# Impression5-SMASH-Shield.net
KiCad netlist of a schematic drawn in EAGLE
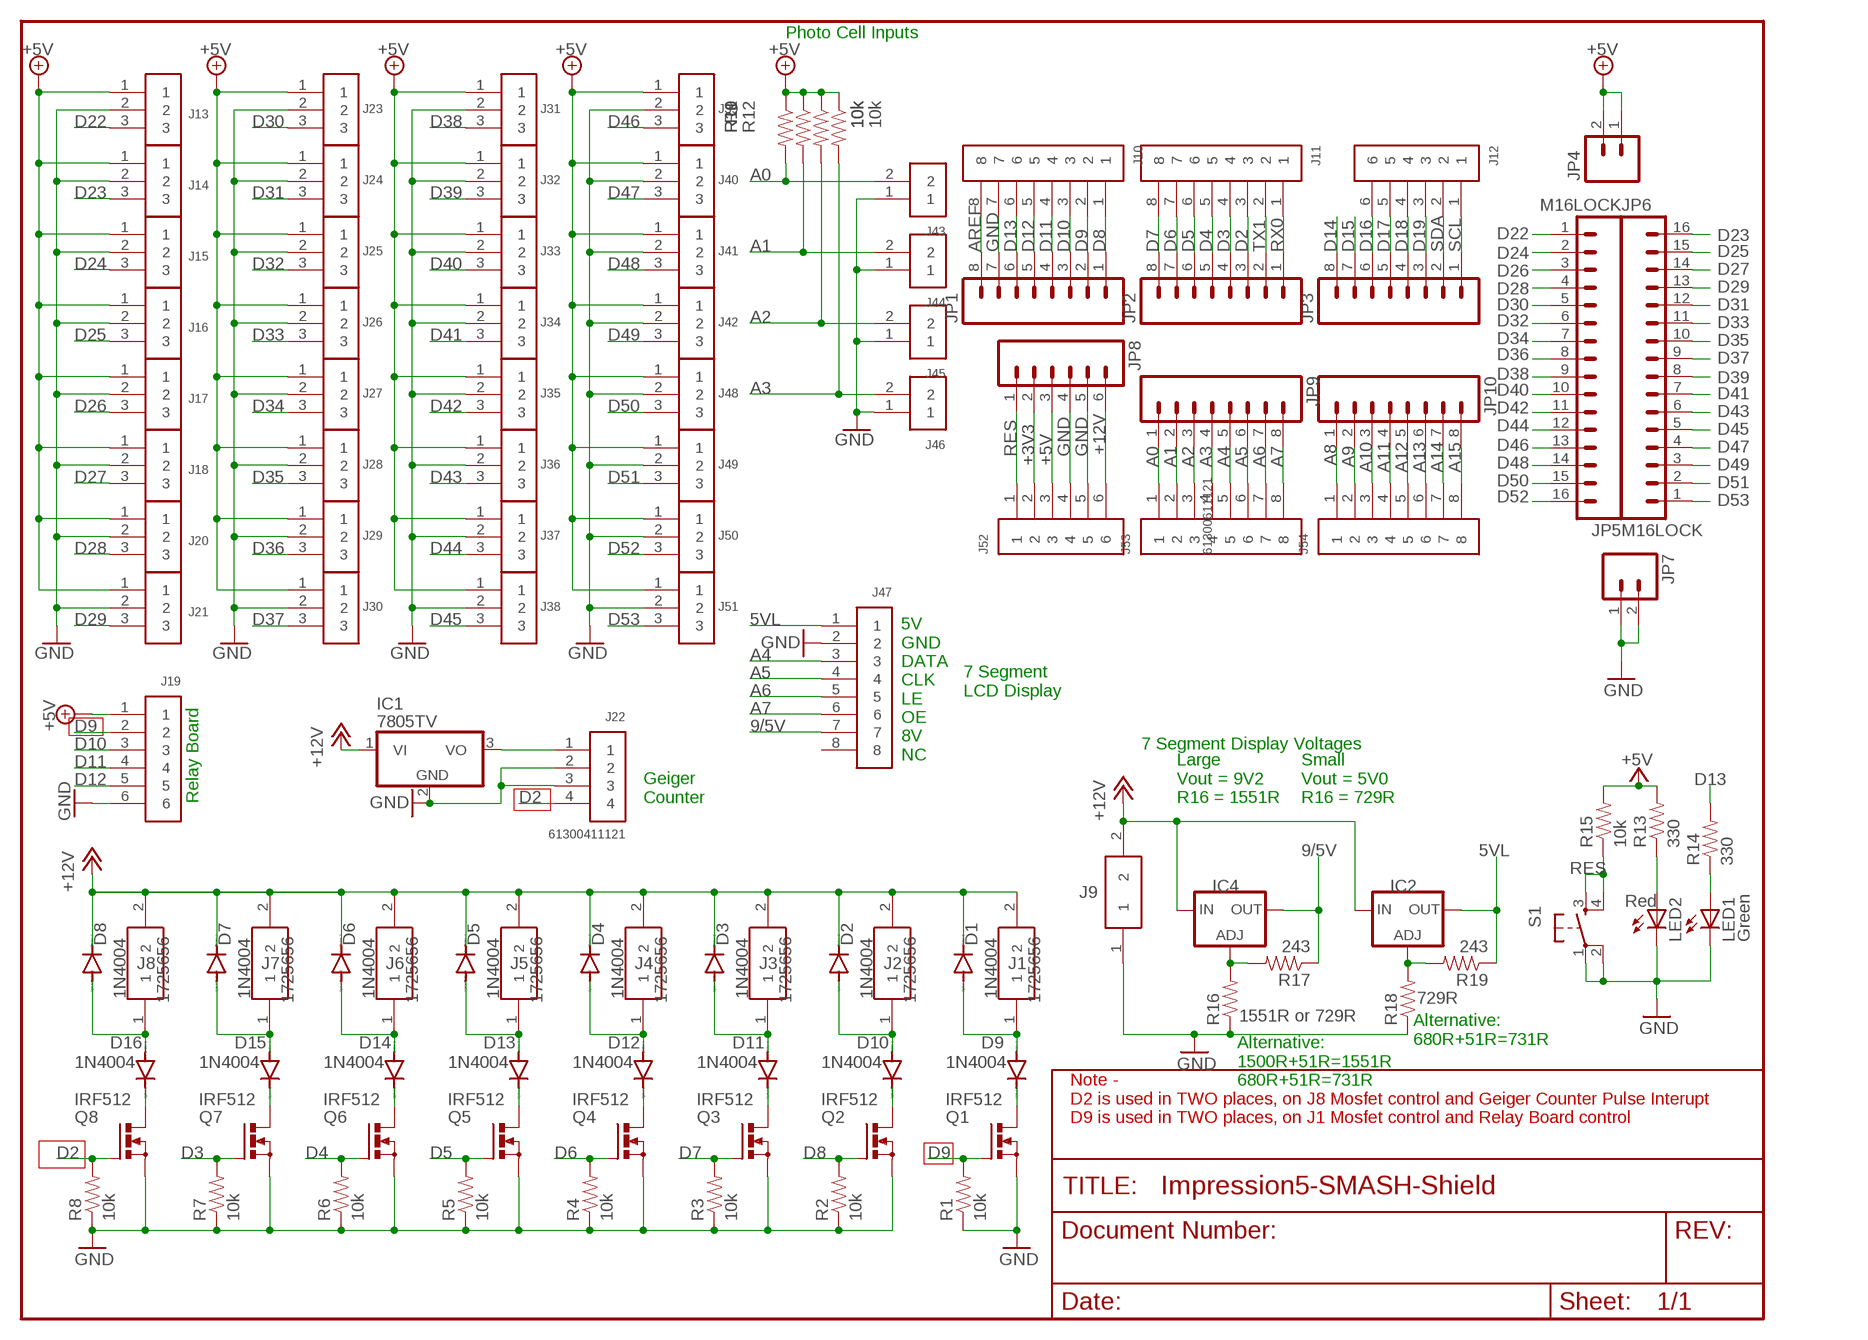
[diagram p0: schematic, sheet 1]

(export (version "E")
  (design (tool "Eeschema 10.0.6"))
  (components
    (comp (ref "D1")
      (value "1N4004")
      (footprint "eagle-import:DO41-10")
      (libsource (lib "eagle-import") (part "1N4004"))
    )
    (comp (ref "D2")
      (value "1N4004")
      (footprint "eagle-import:DO41-10")
      (libsource (lib "eagle-import") (part "1N4004"))
    )
    (comp (ref "D3")
      (value "1N4004")
      (footprint "eagle-import:DO41-10")
      (libsource (lib "eagle-import") (part "1N4004"))
    )
    (comp (ref "D4")
      (value "1N4004")
      (footprint "eagle-import:DO41-10")
      (libsource (lib "eagle-import") (part "1N4004"))
    )
    (comp (ref "D5")
      (value "1N4004")
      (footprint "eagle-import:DO41-10")
      (libsource (lib "eagle-import") (part "1N4004"))
    )
    (comp (ref "D6")
      (value "1N4004")
      (footprint "eagle-import:DO41-10")
      (libsource (lib "eagle-import") (part "1N4004"))
    )
    (comp (ref "D7")
      (value "1N4004")
      (footprint "eagle-import:DO41-10")
      (libsource (lib "eagle-import") (part "1N4004"))
    )
    (comp (ref "D8")
      (value "1N4004")
      (footprint "eagle-import:DO41-10")
      (libsource (lib "eagle-import") (part "1N4004"))
    )
    (comp (ref "D9")
      (value "1N4004")
      (footprint "eagle-import:DO41-10")
      (libsource (lib "eagle-import") (part "1N4004"))
    )
    (comp (ref "D10")
      (value "1N4004")
      (footprint "eagle-import:DO41-10")
      (libsource (lib "eagle-import") (part "1N4004"))
    )
    (comp (ref "D11")
      (value "1N4004")
      (footprint "eagle-import:DO41-10")
      (libsource (lib "eagle-import") (part "1N4004"))
    )
    (comp (ref "D12")
      (value "1N4004")
      (footprint "eagle-import:DO41-10")
      (libsource (lib "eagle-import") (part "1N4004"))
    )
    (comp (ref "D13")
      (value "1N4004")
      (footprint "eagle-import:DO41-10")
      (libsource (lib "eagle-import") (part "1N4004"))
    )
    (comp (ref "D14")
      (value "1N4004")
      (footprint "eagle-import:DO41-10")
      (libsource (lib "eagle-import") (part "1N4004"))
    )
    (comp (ref "D15")
      (value "1N4004")
      (footprint "eagle-import:DO41-10")
      (libsource (lib "eagle-import") (part "1N4004"))
    )
    (comp (ref "D16")
      (value "1N4004")
      (footprint "eagle-import:DO41-10")
      (libsource (lib "eagle-import") (part "1N4004"))
    )
    (comp (ref "IC1")
      (value "7805TV")
      (footprint "eagle-import:TO220V")
      (libsource (lib "eagle-import") (part "78TV05"))
    )
    (comp (ref "IC2")
      (value "LM317TS")
      (footprint "eagle-import:317TS")
      (libsource (lib "eagle-import") (part "LM317TS"))
    )
    (comp (ref "IC4")
      (value "LM317TS")
      (footprint "eagle-import:317TS")
      (libsource (lib "eagle-import") (part "LM317TS"))
    )
    (comp (ref "J1")
      (value "1725656")
      (footprint "eagle-import:1725656")
      (fields (field (name "MOUSER_PART_NUMBER") "651-1725656") (field (name "RS_PART_NUMBER") "3909023"))
      (libsource (lib "eagle-import") (part "1725656"))
    )
    (comp (ref "J2")
      (value "1725656")
      (footprint "eagle-import:1725656")
      (fields (field (name "MOUSER_PART_NUMBER") "651-1725656") (field (name "RS_PART_NUMBER") "3909023"))
      (libsource (lib "eagle-import") (part "1725656"))
    )
    (comp (ref "J3")
      (value "1725656")
      (footprint "eagle-import:1725656")
      (fields (field (name "MOUSER_PART_NUMBER") "651-1725656") (field (name "RS_PART_NUMBER") "3909023"))
      (libsource (lib "eagle-import") (part "1725656"))
    )
    (comp (ref "J4")
      (value "1725656")
      (footprint "eagle-import:1725656")
      (fields (field (name "MOUSER_PART_NUMBER") "651-1725656") (field (name "RS_PART_NUMBER") "3909023"))
      (libsource (lib "eagle-import") (part "1725656"))
    )
    (comp (ref "J5")
      (value "1725656")
      (footprint "eagle-import:1725656")
      (fields (field (name "MOUSER_PART_NUMBER") "651-1725656") (field (name "RS_PART_NUMBER") "3909023"))
      (libsource (lib "eagle-import") (part "1725656"))
    )
    (comp (ref "J6")
      (value "1725656")
      (footprint "eagle-import:1725656")
      (fields (field (name "MOUSER_PART_NUMBER") "651-1725656") (field (name "RS_PART_NUMBER") "3909023"))
      (libsource (lib "eagle-import") (part "1725656"))
    )
    (comp (ref "J7")
      (value "1725656")
      (footprint "eagle-import:1725656")
      (fields (field (name "MOUSER_PART_NUMBER") "651-1725656") (field (name "RS_PART_NUMBER") "3909023"))
      (libsource (lib "eagle-import") (part "1725656"))
    )
    (comp (ref "J8")
      (value "1725656")
      (footprint "eagle-import:1725656")
      (fields (field (name "MOUSER_PART_NUMBER") "651-1725656") (field (name "RS_PART_NUMBER") "3909023"))
      (libsource (lib "eagle-import") (part "1725656"))
    )
    (comp (ref "J9")
      (value "1725656")
      (footprint "eagle-import:1725656")
      (fields (field (name "MOUSER_PART_NUMBER") "651-1725656") (field (name "RS_PART_NUMBER") "3909023"))
      (libsource (lib "eagle-import") (part "1725656"))
    )
    (comp (ref "J10")
      (value "61300811121")
      (footprint "eagle-import:61300811121")
      (fields
        (field (name "DIGI_KEY_PART_NUMBER") "732-5321-ND")
        (field (name "MANUFACTURER") "Wurth Electronics Inc.")
      )
      (libsource (lib "eagle-import") (part "61300811121"))
    )
    (comp (ref "J11")
      (value "61300811121")
      (footprint "eagle-import:61300811121")
      (fields
        (field (name "DIGI_KEY_PART_NUMBER") "732-5321-ND")
        (field (name "MANUFACTURER") "Wurth Electronics Inc.")
      )
      (libsource (lib "eagle-import") (part "61300811121"))
    )
    (comp (ref "J12")
      (value "61300611121")
      (footprint "eagle-import:61300611121")
      (fields
        (field (name "DIGI_KEY_PART_NUMBER") "732-5319-ND")
        (field (name "MANUFACTURER") "Wurth Electronics Inc.")
      )
      (libsource (lib "eagle-import") (part "61300611121"))
    )
    (comp (ref "J13")
      (value "61300311121")
      (footprint "eagle-import:61300311121")
      (fields
        (field (name "DIGI_KEY_PART_NUMBER") "732-5316-ND")
        (field (name "MANUFACTURER") "Wurth Electronics Inc.")
      )
      (libsource (lib "eagle-import") (part "61300311121"))
    )
    (comp (ref "J14")
      (value "61300311121")
      (footprint "eagle-import:61300311121")
      (fields
        (field (name "DIGI_KEY_PART_NUMBER") "732-5316-ND")
        (field (name "MANUFACTURER") "Wurth Electronics Inc.")
      )
      (libsource (lib "eagle-import") (part "61300311121"))
    )
    (comp (ref "J15")
      (value "61300311121")
      (footprint "eagle-import:61300311121")
      (fields
        (field (name "DIGI_KEY_PART_NUMBER") "732-5316-ND")
        (field (name "MANUFACTURER") "Wurth Electronics Inc.")
      )
      (libsource (lib "eagle-import") (part "61300311121"))
    )
    (comp (ref "J16")
      (value "61300311121")
      (footprint "eagle-import:61300311121")
      (fields
        (field (name "DIGI_KEY_PART_NUMBER") "732-5316-ND")
        (field (name "MANUFACTURER") "Wurth Electronics Inc.")
      )
      (libsource (lib "eagle-import") (part "61300311121"))
    )
    (comp (ref "J17")
      (value "61300311121")
      (footprint "eagle-import:61300311121")
      (fields
        (field (name "DIGI_KEY_PART_NUMBER") "732-5316-ND")
        (field (name "MANUFACTURER") "Wurth Electronics Inc.")
      )
      (libsource (lib "eagle-import") (part "61300311121"))
    )
    (comp (ref "J18")
      (value "61300311121")
      (footprint "eagle-import:61300311121")
      (fields
        (field (name "DIGI_KEY_PART_NUMBER") "732-5316-ND")
        (field (name "MANUFACTURER") "Wurth Electronics Inc.")
      )
      (libsource (lib "eagle-import") (part "61300311121"))
    )
    (comp (ref "J19")
      (value "61300611121")
      (footprint "eagle-import:61300611121")
      (fields
        (field (name "DIGI_KEY_PART_NUMBER") "732-5319-ND")
        (field (name "MANUFACTURER") "Wurth Electronics Inc.")
      )
      (libsource (lib "eagle-import") (part "61300611121"))
    )
    (comp (ref "J20")
      (value "61300311121")
      (footprint "eagle-import:61300311121")
      (fields
        (field (name "DIGI_KEY_PART_NUMBER") "732-5316-ND")
        (field (name "MANUFACTURER") "Wurth Electronics Inc.")
      )
      (libsource (lib "eagle-import") (part "61300311121"))
    )
    (comp (ref "J21")
      (value "61300311121")
      (footprint "eagle-import:61300311121")
      (fields
        (field (name "DIGI_KEY_PART_NUMBER") "732-5316-ND")
        (field (name "MANUFACTURER") "Wurth Electronics Inc.")
      )
      (libsource (lib "eagle-import") (part "61300311121"))
    )
    (comp (ref "J22")
      (value "61300411121")
      (footprint "eagle-import:61300411121")
      (fields
        (field (name "DIGI_KEY_PART_NUMBER") "732-5317-ND")
        (field (name "MANUFACTURER") "Wurth Electronics Inc.")
      )
      (libsource (lib "eagle-import") (part "61300411121"))
    )
    (comp (ref "J23")
      (value "61300311121")
      (footprint "eagle-import:61300311121")
      (fields
        (field (name "DIGI_KEY_PART_NUMBER") "732-5316-ND")
        (field (name "MANUFACTURER") "Wurth Electronics Inc.")
      )
      (libsource (lib "eagle-import") (part "61300311121"))
    )
    (comp (ref "J24")
      (value "61300311121")
      (footprint "eagle-import:61300311121")
      (fields
        (field (name "DIGI_KEY_PART_NUMBER") "732-5316-ND")
        (field (name "MANUFACTURER") "Wurth Electronics Inc.")
      )
      (libsource (lib "eagle-import") (part "61300311121"))
    )
    (comp (ref "J25")
      (value "61300311121")
      (footprint "eagle-import:61300311121")
      (fields
        (field (name "DIGI_KEY_PART_NUMBER") "732-5316-ND")
        (field (name "MANUFACTURER") "Wurth Electronics Inc.")
      )
      (libsource (lib "eagle-import") (part "61300311121"))
    )
    (comp (ref "J26")
      (value "61300311121")
      (footprint "eagle-import:61300311121")
      (fields
        (field (name "DIGI_KEY_PART_NUMBER") "732-5316-ND")
        (field (name "MANUFACTURER") "Wurth Electronics Inc.")
      )
      (libsource (lib "eagle-import") (part "61300311121"))
    )
    (comp (ref "J27")
      (value "61300311121")
      (footprint "eagle-import:61300311121")
      (fields
        (field (name "DIGI_KEY_PART_NUMBER") "732-5316-ND")
        (field (name "MANUFACTURER") "Wurth Electronics Inc.")
      )
      (libsource (lib "eagle-import") (part "61300311121"))
    )
    (comp (ref "J28")
      (value "61300311121")
      (footprint "eagle-import:61300311121")
      (fields
        (field (name "DIGI_KEY_PART_NUMBER") "732-5316-ND")
        (field (name "MANUFACTURER") "Wurth Electronics Inc.")
      )
      (libsource (lib "eagle-import") (part "61300311121"))
    )
    (comp (ref "J29")
      (value "61300311121")
      (footprint "eagle-import:61300311121")
      (fields
        (field (name "DIGI_KEY_PART_NUMBER") "732-5316-ND")
        (field (name "MANUFACTURER") "Wurth Electronics Inc.")
      )
      (libsource (lib "eagle-import") (part "61300311121"))
    )
    (comp (ref "J30")
      (value "61300311121")
      (footprint "eagle-import:61300311121")
      (fields
        (field (name "DIGI_KEY_PART_NUMBER") "732-5316-ND")
        (field (name "MANUFACTURER") "Wurth Electronics Inc.")
      )
      (libsource (lib "eagle-import") (part "61300311121"))
    )
    (comp (ref "J31")
      (value "61300311121")
      (footprint "eagle-import:61300311121")
      (fields
        (field (name "DIGI_KEY_PART_NUMBER") "732-5316-ND")
        (field (name "MANUFACTURER") "Wurth Electronics Inc.")
      )
      (libsource (lib "eagle-import") (part "61300311121"))
    )
    (comp (ref "J32")
      (value "61300311121")
      (footprint "eagle-import:61300311121")
      (fields
        (field (name "DIGI_KEY_PART_NUMBER") "732-5316-ND")
        (field (name "MANUFACTURER") "Wurth Electronics Inc.")
      )
      (libsource (lib "eagle-import") (part "61300311121"))
    )
    (comp (ref "J33")
      (value "61300311121")
      (footprint "eagle-import:61300311121")
      (fields
        (field (name "DIGI_KEY_PART_NUMBER") "732-5316-ND")
        (field (name "MANUFACTURER") "Wurth Electronics Inc.")
      )
      (libsource (lib "eagle-import") (part "61300311121"))
    )
    (comp (ref "J34")
      (value "61300311121")
      (footprint "eagle-import:61300311121")
      (fields
        (field (name "DIGI_KEY_PART_NUMBER") "732-5316-ND")
        (field (name "MANUFACTURER") "Wurth Electronics Inc.")
      )
      (libsource (lib "eagle-import") (part "61300311121"))
    )
    (comp (ref "J35")
      (value "61300311121")
      (footprint "eagle-import:61300311121")
      (fields
        (field (name "DIGI_KEY_PART_NUMBER") "732-5316-ND")
        (field (name "MANUFACTURER") "Wurth Electronics Inc.")
      )
      (libsource (lib "eagle-import") (part "61300311121"))
    )
    (comp (ref "J36")
      (value "61300311121")
      (footprint "eagle-import:61300311121")
      (fields
        (field (name "DIGI_KEY_PART_NUMBER") "732-5316-ND")
        (field (name "MANUFACTURER") "Wurth Electronics Inc.")
      )
      (libsource (lib "eagle-import") (part "61300311121"))
    )
    (comp (ref "J37")
      (value "61300311121")
      (footprint "eagle-import:61300311121")
      (fields
        (field (name "DIGI_KEY_PART_NUMBER") "732-5316-ND")
        (field (name "MANUFACTURER") "Wurth Electronics Inc.")
      )
      (libsource (lib "eagle-import") (part "61300311121"))
    )
    (comp (ref "J38")
      (value "61300311121")
      (footprint "eagle-import:61300311121")
      (fields
        (field (name "DIGI_KEY_PART_NUMBER") "732-5316-ND")
        (field (name "MANUFACTURER") "Wurth Electronics Inc.")
      )
      (libsource (lib "eagle-import") (part "61300311121"))
    )
    (comp (ref "J39")
      (value "61300311121")
      (footprint "eagle-import:61300311121")
      (fields
        (field (name "DIGI_KEY_PART_NUMBER") "732-5316-ND")
        (field (name "MANUFACTURER") "Wurth Electronics Inc.")
      )
      (libsource (lib "eagle-import") (part "61300311121"))
    )
    (comp (ref "J40")
      (value "61300311121")
      (footprint "eagle-import:61300311121")
      (fields
        (field (name "DIGI_KEY_PART_NUMBER") "732-5316-ND")
        (field (name "MANUFACTURER") "Wurth Electronics Inc.")
      )
      (libsource (lib "eagle-import") (part "61300311121"))
    )
    (comp (ref "J41")
      (value "61300311121")
      (footprint "eagle-import:61300311121")
      (fields
        (field (name "DIGI_KEY_PART_NUMBER") "732-5316-ND")
        (field (name "MANUFACTURER") "Wurth Electronics Inc.")
      )
      (libsource (lib "eagle-import") (part "61300311121"))
    )
    (comp (ref "J42")
      (value "61300311121")
      (footprint "eagle-import:61300311121")
      (fields
        (field (name "DIGI_KEY_PART_NUMBER") "732-5316-ND")
        (field (name "MANUFACTURER") "Wurth Electronics Inc.")
      )
      (libsource (lib "eagle-import") (part "61300311121"))
    )
    (comp (ref "J43")
      (value "61300211121")
      (footprint "eagle-import:61300211121")
      (fields
        (field (name "DIGI_KEY_PART_NUMBER") "732-5315-ND")
        (field (name "MANUFACTURER") "Wurth Electronics Inc.")
      )
      (libsource (lib "eagle-import") (part "61300211121"))
    )
    (comp (ref "J44")
      (value "61300211121")
      (footprint "eagle-import:61300211121")
      (fields
        (field (name "DIGI_KEY_PART_NUMBER") "732-5315-ND")
        (field (name "MANUFACTURER") "Wurth Electronics Inc.")
      )
      (libsource (lib "eagle-import") (part "61300211121"))
    )
    (comp (ref "J45")
      (value "61300211121")
      (footprint "eagle-import:61300211121")
      (fields
        (field (name "DIGI_KEY_PART_NUMBER") "732-5315-ND")
        (field (name "MANUFACTURER") "Wurth Electronics Inc.")
      )
      (libsource (lib "eagle-import") (part "61300211121"))
    )
    (comp (ref "J46")
      (value "61300211121")
      (footprint "eagle-import:61300211121")
      (fields
        (field (name "DIGI_KEY_PART_NUMBER") "732-5315-ND")
        (field (name "MANUFACTURER") "Wurth Electronics Inc.")
      )
      (libsource (lib "eagle-import") (part "61300211121"))
    )
    (comp (ref "J47")
      (value "61300811121")
      (footprint "eagle-import:61300811121")
      (fields
        (field (name "DIGI_KEY_PART_NUMBER") "732-5321-ND")
        (field (name "MANUFACTURER") "Wurth Electronics Inc.")
      )
      (libsource (lib "eagle-import") (part "61300811121"))
    )
    (comp (ref "J48")
      (value "61300311121")
      (footprint "eagle-import:61300311121")
      (fields
        (field (name "DIGI_KEY_PART_NUMBER") "732-5316-ND")
        (field (name "MANUFACTURER") "Wurth Electronics Inc.")
      )
      (libsource (lib "eagle-import") (part "61300311121"))
    )
    (comp (ref "J49")
      (value "61300311121")
      (footprint "eagle-import:61300311121")
      (fields
        (field (name "DIGI_KEY_PART_NUMBER") "732-5316-ND")
        (field (name "MANUFACTURER") "Wurth Electronics Inc.")
      )
      (libsource (lib "eagle-import") (part "61300311121"))
    )
    (comp (ref "J50")
      (value "61300311121")
      (footprint "eagle-import:61300311121")
      (fields
        (field (name "DIGI_KEY_PART_NUMBER") "732-5316-ND")
        (field (name "MANUFACTURER") "Wurth Electronics Inc.")
      )
      (libsource (lib "eagle-import") (part "61300311121"))
    )
    (comp (ref "J51")
      (value "61300311121")
      (footprint "eagle-import:61300311121")
      (fields
        (field (name "DIGI_KEY_PART_NUMBER") "732-5316-ND")
        (field (name "MANUFACTURER") "Wurth Electronics Inc.")
      )
      (libsource (lib "eagle-import") (part "61300311121"))
    )
    (comp (ref "J52")
      (value "61300611121")
      (footprint "eagle-import:61300611121")
      (fields
        (field (name "DIGI_KEY_PART_NUMBER") "732-5319-ND")
        (field (name "MANUFACTURER") "Wurth Electronics Inc.")
      )
      (libsource (lib "eagle-import") (part "61300611121"))
    )
    (comp (ref "J53")
      (value "61300811121")
      (footprint "eagle-import:61300811121")
      (fields
        (field (name "DIGI_KEY_PART_NUMBER") "732-5321-ND")
        (field (name "MANUFACTURER") "Wurth Electronics Inc.")
      )
      (libsource (lib "eagle-import") (part "61300811121"))
    )
    (comp (ref "J54")
      (value "61300811121")
      (footprint "eagle-import:61300811121")
      (fields
        (field (name "DIGI_KEY_PART_NUMBER") "732-5321-ND")
        (field (name "MANUFACTURER") "Wurth Electronics Inc.")
      )
      (libsource (lib "eagle-import") (part "61300811121"))
    )
    (comp (ref "JP1")
      (value "M08LOCK")
      (footprint "eagle-import:1X08_LOCK")
      (libsource (lib "eagle-import") (part "M08LOCK"))
    )
    (comp (ref "JP2")
      (value "M08LOCK")
      (footprint "eagle-import:1X08_LOCK")
      (libsource (lib "eagle-import") (part "M08LOCK"))
    )
    (comp (ref "JP3")
      (value "M08LOCK")
      (footprint "eagle-import:1X08_LOCK")
      (libsource (lib "eagle-import") (part "M08LOCK"))
    )
    (comp (ref "JP4")
      (value "M02LOCK")
      (footprint "eagle-import:1X02_LOCK")
      (libsource (lib "eagle-import") (part "M02LOCK"))
    )
    (comp (ref "JP5")
      (value "M16LOCK")
      (footprint "eagle-import:1X16_LOCK")
      (libsource (lib "eagle-import") (part "M16LOCK"))
    )
    (comp (ref "JP6")
      (value "M16LOCK")
      (footprint "eagle-import:1X16_LOCK")
      (libsource (lib "eagle-import") (part "M16LOCK"))
    )
    (comp (ref "JP7")
      (value "M02LOCK")
      (footprint "eagle-import:1X02_LOCK")
      (libsource (lib "eagle-import") (part "M02LOCK"))
    )
    (comp (ref "JP8")
      (value "M06LOCK")
      (footprint "eagle-import:1X06_LOCK")
      (libsource (lib "eagle-import") (part "M06LOCK"))
    )
    (comp (ref "JP9")
      (value "M08LOCK")
      (footprint "eagle-import:1X08_LOCK")
      (libsource (lib "eagle-import") (part "M08LOCK"))
    )
    (comp (ref "JP10")
      (value "M08LOCK")
      (footprint "eagle-import:1X08_LOCK")
      (libsource (lib "eagle-import") (part "M08LOCK"))
    )
    (comp (ref "LED1")
      (value "Green")
      (footprint "eagle-import:LED5MM")
      (libsource (lib "eagle-import") (part "LED5MM"))
    )
    (comp (ref "LED2")
      (value "Red")
      (footprint "eagle-import:LED5MM")
      (libsource (lib "eagle-import") (part "LED5MM"))
    )
    (comp (ref "Q1")
      (value "IRF512")
      (footprint "eagle-import:TO220BV")
      (libsource (lib "eagle-import") (part "IRF512"))
    )
    (comp (ref "Q2")
      (value "IRF512")
      (footprint "eagle-import:TO220BV")
      (libsource (lib "eagle-import") (part "IRF512"))
    )
    (comp (ref "Q3")
      (value "IRF512")
      (footprint "eagle-import:TO220BV")
      (libsource (lib "eagle-import") (part "IRF512"))
    )
    (comp (ref "Q4")
      (value "IRF512")
      (footprint "eagle-import:TO220BV")
      (libsource (lib "eagle-import") (part "IRF512"))
    )
    (comp (ref "Q5")
      (value "IRF512")
      (footprint "eagle-import:TO220BV")
      (libsource (lib "eagle-import") (part "IRF512"))
    )
    (comp (ref "Q6")
      (value "IRF512")
      (footprint "eagle-import:TO220BV")
      (libsource (lib "eagle-import") (part "IRF512"))
    )
    (comp (ref "Q7")
      (value "IRF512")
      (footprint "eagle-import:TO220BV")
      (libsource (lib "eagle-import") (part "IRF512"))
    )
    (comp (ref "Q8")
      (value "IRF512")
      (footprint "eagle-import:TO220BV")
      (libsource (lib "eagle-import") (part "IRF512"))
    )
    (comp (ref "R1")
      (value "10k")
      (footprint "eagle-import:AXIAL-0.3")
      (libsource (lib "eagle-import") (part "RESISTORPTH1"))
    )
    (comp (ref "R2")
      (value "10k")
      (footprint "eagle-import:AXIAL-0.3")
      (libsource (lib "eagle-import") (part "RESISTORPTH1"))
    )
    (comp (ref "R3")
      (value "10k")
      (footprint "eagle-import:AXIAL-0.3")
      (libsource (lib "eagle-import") (part "RESISTORPTH1"))
    )
    (comp (ref "R4")
      (value "10k")
      (footprint "eagle-import:AXIAL-0.3")
      (libsource (lib "eagle-import") (part "RESISTORPTH1"))
    )
    (comp (ref "R5")
      (value "10k")
      (footprint "eagle-import:AXIAL-0.3")
      (libsource (lib "eagle-import") (part "RESISTORPTH1"))
    )
    (comp (ref "R6")
      (value "10k")
      (footprint "eagle-import:AXIAL-0.3")
      (libsource (lib "eagle-import") (part "RESISTORPTH1"))
    )
    (comp (ref "R7")
      (value "10k")
      (footprint "eagle-import:AXIAL-0.3")
      (libsource (lib "eagle-import") (part "RESISTORPTH1"))
    )
    (comp (ref "R8")
      (value "10k")
      (footprint "eagle-import:AXIAL-0.3")
      (libsource (lib "eagle-import") (part "RESISTORPTH1"))
    )
    (comp (ref "R9")
      (value "10k")
      (footprint "eagle-import:AXIAL-0.3")
      (libsource (lib "eagle-import") (part "RESISTORPTH1"))
    )
    (comp (ref "R10")
      (value "10k")
      (footprint "eagle-import:AXIAL-0.3")
      (libsource (lib "eagle-import") (part "RESISTORPTH1"))
    )
    (comp (ref "R11")
      (value "10k")
      (footprint "eagle-import:AXIAL-0.3")
      (libsource (lib "eagle-import") (part "RESISTORPTH1"))
    )
    (comp (ref "R12")
      (value "10k")
      (footprint "eagle-import:AXIAL-0.3")
      (libsource (lib "eagle-import") (part "RESISTORPTH1"))
    )
    (comp (ref "R13")
      (value "330")
      (footprint "eagle-import:AXIAL-0.3")
      (libsource (lib "eagle-import") (part "RESISTORPTH1"))
    )
    (comp (ref "R14")
      (value "330")
      (footprint "eagle-import:AXIAL-0.3")
      (libsource (lib "eagle-import") (part "RESISTORPTH1"))
    )
    (comp (ref "R15")
      (value "10k")
      (footprint "eagle-import:AXIAL-0.3")
      (libsource (lib "eagle-import") (part "RESISTORPTH1"))
    )
    (comp (ref "R16")
      (value "1551R or 729R")
      (footprint "eagle-import:AXIAL-0.3")
      (libsource (lib "eagle-import") (part "RESISTORPTH1"))
    )
    (comp (ref "R17")
      (value "243")
      (footprint "eagle-import:AXIAL-0.3")
      (libsource (lib "eagle-import") (part "RESISTORPTH1"))
    )
    (comp (ref "R18")
      (value "729R")
      (footprint "eagle-import:AXIAL-0.3")
      (libsource (lib "eagle-import") (part "RESISTORPTH1"))
    )
    (comp (ref "R19")
      (value "243")
      (footprint "eagle-import:AXIAL-0.3")
      (libsource (lib "eagle-import") (part "RESISTORPTH1"))
    )
    (comp (ref "S1")
      (value "TAC_SWITCHPTH")
      (footprint "eagle-import:TACTILE-PTH")
      (libsource (lib "eagle-import") (part "TAC_SWITCHPTH"))
    )
  )
  (nets
    (net (code "1") (name "+5V") (class "Default")
      (node (ref "J13") (pin "1") (pinfunction "1_1") (pintype "passive"))
      (node (ref "J14") (pin "1") (pinfunction "1_1") (pintype "passive"))
      (node (ref "J15") (pin "1") (pinfunction "1_1") (pintype "passive"))
      (node (ref "J16") (pin "1") (pinfunction "1_1") (pintype "passive"))
      (node (ref "J17") (pin "1") (pinfunction "1_1") (pintype "passive"))
      (node (ref "J18") (pin "1") (pinfunction "1_1") (pintype "passive"))
      (node (ref "J19") (pin "1") (pinfunction "1_1") (pintype "passive"))
      (node (ref "J20") (pin "1") (pinfunction "1_1") (pintype "passive"))
      (node (ref "J21") (pin "1") (pinfunction "1_1") (pintype "passive"))
      (node (ref "J23") (pin "1") (pinfunction "1_1") (pintype "passive"))
      (node (ref "J24") (pin "1") (pinfunction "1_1") (pintype "passive"))
      (node (ref "J25") (pin "1") (pinfunction "1_1") (pintype "passive"))
      (node (ref "J26") (pin "1") (pinfunction "1_1") (pintype "passive"))
      (node (ref "J27") (pin "1") (pinfunction "1_1") (pintype "passive"))
      (node (ref "J28") (pin "1") (pinfunction "1_1") (pintype "passive"))
      (node (ref "J29") (pin "1") (pinfunction "1_1") (pintype "passive"))
      (node (ref "J30") (pin "1") (pinfunction "1_1") (pintype "passive"))
      (node (ref "J31") (pin "1") (pinfunction "1_1") (pintype "passive"))
      (node (ref "J32") (pin "1") (pinfunction "1_1") (pintype "passive"))
      (node (ref "J33") (pin "1") (pinfunction "1_1") (pintype "passive"))
      (node (ref "J34") (pin "1") (pinfunction "1_1") (pintype "passive"))
      (node (ref "J35") (pin "1") (pinfunction "1_1") (pintype "passive"))
      (node (ref "J36") (pin "1") (pinfunction "1_1") (pintype "passive"))
      (node (ref "J37") (pin "1") (pinfunction "1_1") (pintype "passive"))
      (node (ref "J38") (pin "1") (pinfunction "1_1") (pintype "passive"))
      (node (ref "J39") (pin "1") (pinfunction "1_1") (pintype "passive"))
      (node (ref "J40") (pin "1") (pinfunction "1_1") (pintype "passive"))
      (node (ref "J41") (pin "1") (pinfunction "1_1") (pintype "passive"))
      (node (ref "J42") (pin "1") (pinfunction "1_1") (pintype "passive"))
      (node (ref "J48") (pin "1") (pinfunction "1_1") (pintype "passive"))
      (node (ref "J49") (pin "1") (pinfunction "1_1") (pintype "passive"))
      (node (ref "J50") (pin "1") (pinfunction "1_1") (pintype "passive"))
      (node (ref "J51") (pin "1") (pinfunction "1_1") (pintype "passive"))
      (node (ref "J52") (pin "3") (pinfunction "3_3") (pintype "passive"))
      (node (ref "JP4") (pin "1") (pinfunction "1_1") (pintype "passive"))
      (node (ref "JP4") (pin "2") (pinfunction "2_2") (pintype "passive"))
      (node (ref "JP8") (pin "3") (pinfunction "3_3") (pintype "passive"))
      (node (ref "R10") (pin "P$1") (pinfunction "1_P$1") (pintype "passive"))
      (node (ref "R11") (pin "P$1") (pinfunction "1_P$1") (pintype "passive"))
      (node (ref "R12") (pin "P$1") (pinfunction "1_P$1") (pintype "passive"))
      (node (ref "R13") (pin "P$2") (pinfunction "2_P$2") (pintype "passive"))
      (node (ref "R15") (pin "P$2") (pinfunction "2_P$2") (pintype "passive"))
      (node (ref "R9") (pin "P$1") (pinfunction "1_P$1") (pintype "passive"))
    )
    (net (code "2") (name "+12V") (class "Default")
      (node (ref "D1") (pin "C") (pinfunction "C_C") (pintype "passive"))
      (node (ref "D2") (pin "C") (pinfunction "C_C") (pintype "passive"))
      (node (ref "D3") (pin "C") (pinfunction "C_C") (pintype "passive"))
      (node (ref "D4") (pin "C") (pinfunction "C_C") (pintype "passive"))
      (node (ref "D5") (pin "C") (pinfunction "C_C") (pintype "passive"))
      (node (ref "D6") (pin "C") (pinfunction "C_C") (pintype "passive"))
      (node (ref "D7") (pin "C") (pinfunction "C_C") (pintype "passive"))
      (node (ref "D8") (pin "C") (pinfunction "C_C") (pintype "passive"))
      (node (ref "IC1") (pin "1") (pinfunction "VI_1") (pintype "input"))
      (node (ref "IC2") (pin "3") (pinfunction "IN_3") (pintype "input"))
      (node (ref "IC4") (pin "3") (pinfunction "IN_3") (pintype "input"))
      (node (ref "J1") (pin "2") (pinfunction "2_2") (pintype "bidirectional"))
      (node (ref "J2") (pin "2") (pinfunction "2_2") (pintype "bidirectional"))
      (node (ref "J3") (pin "2") (pinfunction "2_2") (pintype "bidirectional"))
      (node (ref "J4") (pin "2") (pinfunction "2_2") (pintype "bidirectional"))
      (node (ref "J5") (pin "2") (pinfunction "2_2") (pintype "bidirectional"))
      (node (ref "J52") (pin "6") (pinfunction "6_6") (pintype "passive"))
      (node (ref "J6") (pin "2") (pinfunction "2_2") (pintype "bidirectional"))
      (node (ref "J7") (pin "2") (pinfunction "2_2") (pintype "bidirectional"))
      (node (ref "J8") (pin "2") (pinfunction "2_2") (pintype "bidirectional"))
      (node (ref "J9") (pin "2") (pinfunction "2_2") (pintype "bidirectional"))
      (node (ref "JP8") (pin "6") (pinfunction "6_6") (pintype "passive"))
    )
    (net (code "3") (name "/+3V3") (class "Default")
      (node (ref "J52") (pin "2") (pinfunction "2_2") (pintype "passive"))
      (node (ref "JP8") (pin "2") (pinfunction "2_2") (pintype "passive"))
    )
    (net (code "4") (name "/5VL") (class "Default")
      (node (ref "IC2") (pin "2") (pinfunction "OUT_2") (pintype "passive"))
      (node (ref "J47") (pin "1") (pinfunction "1_1") (pintype "passive"))
      (node (ref "R19") (pin "P$1") (pinfunction "1_P$1") (pintype "passive"))
    )
    (net (code "5") (name "/9{slash}5V") (class "Default")
      (node (ref "IC4") (pin "2") (pinfunction "OUT_2") (pintype "passive"))
      (node (ref "J47") (pin "7") (pinfunction "7_7") (pintype "passive"))
      (node (ref "R17") (pin "P$1") (pinfunction "1_P$1") (pintype "passive"))
    )
    (net (code "6") (name "/A0") (class "Default")
      (node (ref "J43") (pin "2") (pinfunction "2_2") (pintype "passive"))
      (node (ref "J53") (pin "1") (pinfunction "1_1") (pintype "passive"))
      (node (ref "JP9") (pin "1") (pinfunction "1_1") (pintype "passive"))
      (node (ref "R9") (pin "P$2") (pinfunction "2_P$2") (pintype "passive"))
    )
    (net (code "7") (name "/A1") (class "Default")
      (node (ref "J44") (pin "2") (pinfunction "2_2") (pintype "passive"))
      (node (ref "J53") (pin "2") (pinfunction "2_2") (pintype "passive"))
      (node (ref "JP9") (pin "2") (pinfunction "2_2") (pintype "passive"))
      (node (ref "R10") (pin "P$2") (pinfunction "2_P$2") (pintype "passive"))
    )
    (net (code "8") (name "/A2") (class "Default")
      (node (ref "J45") (pin "2") (pinfunction "2_2") (pintype "passive"))
      (node (ref "J53") (pin "3") (pinfunction "3_3") (pintype "passive"))
      (node (ref "JP9") (pin "3") (pinfunction "3_3") (pintype "passive"))
      (node (ref "R11") (pin "P$2") (pinfunction "2_P$2") (pintype "passive"))
    )
    (net (code "9") (name "/A3") (class "Default")
      (node (ref "J46") (pin "2") (pinfunction "2_2") (pintype "passive"))
      (node (ref "J53") (pin "4") (pinfunction "4_4") (pintype "passive"))
      (node (ref "JP9") (pin "4") (pinfunction "4_4") (pintype "passive"))
      (node (ref "R12") (pin "P$2") (pinfunction "2_P$2") (pintype "passive"))
    )
    (net (code "10") (name "/A4") (class "Default")
      (node (ref "J47") (pin "3") (pinfunction "3_3") (pintype "passive"))
      (node (ref "J53") (pin "5") (pinfunction "5_5") (pintype "passive"))
      (node (ref "JP9") (pin "5") (pinfunction "5_5") (pintype "passive"))
    )
    (net (code "11") (name "/A5") (class "Default")
      (node (ref "J47") (pin "4") (pinfunction "4_4") (pintype "passive"))
      (node (ref "J53") (pin "6") (pinfunction "6_6") (pintype "passive"))
      (node (ref "JP9") (pin "6") (pinfunction "6_6") (pintype "passive"))
    )
    (net (code "12") (name "/A6") (class "Default")
      (node (ref "J47") (pin "5") (pinfunction "5_5") (pintype "passive"))
      (node (ref "J53") (pin "7") (pinfunction "7_7") (pintype "passive"))
      (node (ref "JP9") (pin "7") (pinfunction "7_7") (pintype "passive"))
    )
    (net (code "13") (name "/A7") (class "Default")
      (node (ref "J47") (pin "6") (pinfunction "6_6") (pintype "passive"))
      (node (ref "J53") (pin "8") (pinfunction "8_8") (pintype "passive"))
      (node (ref "JP9") (pin "8") (pinfunction "8_8") (pintype "passive"))
    )
    (net (code "14") (name "/A8") (class "Default")
      (node (ref "J54") (pin "1") (pinfunction "1_1") (pintype "passive"))
      (node (ref "JP10") (pin "1") (pinfunction "1_1") (pintype "passive"))
    )
    (net (code "15") (name "/A9") (class "Default")
      (node (ref "J54") (pin "2") (pinfunction "2_2") (pintype "passive"))
      (node (ref "JP10") (pin "2") (pinfunction "2_2") (pintype "passive"))
    )
    (net (code "16") (name "/A10") (class "Default")
      (node (ref "J54") (pin "3") (pinfunction "3_3") (pintype "passive"))
      (node (ref "JP10") (pin "3") (pinfunction "3_3") (pintype "passive"))
    )
    (net (code "17") (name "/A11") (class "Default")
      (node (ref "J54") (pin "4") (pinfunction "4_4") (pintype "passive"))
      (node (ref "JP10") (pin "4") (pinfunction "4_4") (pintype "passive"))
    )
    (net (code "18") (name "/A12") (class "Default")
      (node (ref "J54") (pin "5") (pinfunction "5_5") (pintype "passive"))
      (node (ref "JP10") (pin "5") (pinfunction "5_5") (pintype "passive"))
    )
    (net (code "19") (name "/A13") (class "Default")
      (node (ref "J54") (pin "6") (pinfunction "6_6") (pintype "passive"))
      (node (ref "JP10") (pin "6") (pinfunction "6_6") (pintype "passive"))
    )
    (net (code "20") (name "/A14") (class "Default")
      (node (ref "J54") (pin "7") (pinfunction "7_7") (pintype "passive"))
      (node (ref "JP10") (pin "7") (pinfunction "7_7") (pintype "passive"))
    )
    (net (code "21") (name "/A15") (class "Default")
      (node (ref "J54") (pin "8") (pinfunction "8_8") (pintype "passive"))
      (node (ref "JP10") (pin "8") (pinfunction "8_8") (pintype "passive"))
    )
    (net (code "22") (name "/AREF") (class "Default")
      (node (ref "J10") (pin "8") (pinfunction "8_8") (pintype "passive"))
      (node (ref "JP1") (pin "8") (pinfunction "8_8") (pintype "passive"))
    )
    (net (code "23") (name "/D2") (class "Default")
      (node (ref "J11") (pin "3") (pinfunction "3_3") (pintype "passive"))
      (node (ref "J22") (pin "4") (pinfunction "4_4") (pintype "passive"))
      (node (ref "JP2") (pin "3") (pinfunction "3_3") (pintype "passive"))
      (node (ref "Q8") (pin "G") (pinfunction "G_G") (pintype "passive"))
      (node (ref "R8") (pin "P$2") (pinfunction "2_P$2") (pintype "passive"))
    )
    (net (code "24") (name "/D3") (class "Default")
      (node (ref "J11") (pin "4") (pinfunction "4_4") (pintype "passive"))
      (node (ref "JP2") (pin "4") (pinfunction "4_4") (pintype "passive"))
      (node (ref "Q7") (pin "G") (pinfunction "G_G") (pintype "passive"))
      (node (ref "R7") (pin "P$2") (pinfunction "2_P$2") (pintype "passive"))
    )
    (net (code "25") (name "/D4") (class "Default")
      (node (ref "J11") (pin "5") (pinfunction "5_5") (pintype "passive"))
      (node (ref "JP2") (pin "5") (pinfunction "5_5") (pintype "passive"))
      (node (ref "Q6") (pin "G") (pinfunction "G_G") (pintype "passive"))
      (node (ref "R6") (pin "P$2") (pinfunction "2_P$2") (pintype "passive"))
    )
    (net (code "26") (name "/D5") (class "Default")
      (node (ref "J11") (pin "6") (pinfunction "6_6") (pintype "passive"))
      (node (ref "JP2") (pin "6") (pinfunction "6_6") (pintype "passive"))
      (node (ref "Q5") (pin "G") (pinfunction "G_G") (pintype "passive"))
      (node (ref "R5") (pin "P$2") (pinfunction "2_P$2") (pintype "passive"))
    )
    (net (code "27") (name "/D6") (class "Default")
      (node (ref "J11") (pin "7") (pinfunction "7_7") (pintype "passive"))
      (node (ref "JP2") (pin "7") (pinfunction "7_7") (pintype "passive"))
      (node (ref "Q4") (pin "G") (pinfunction "G_G") (pintype "passive"))
      (node (ref "R4") (pin "P$2") (pinfunction "2_P$2") (pintype "passive"))
    )
    (net (code "28") (name "/D7") (class "Default")
      (node (ref "J11") (pin "8") (pinfunction "8_8") (pintype "passive"))
      (node (ref "JP2") (pin "8") (pinfunction "8_8") (pintype "passive"))
      (node (ref "Q3") (pin "G") (pinfunction "G_G") (pintype "passive"))
      (node (ref "R3") (pin "P$2") (pinfunction "2_P$2") (pintype "passive"))
    )
    (net (code "29") (name "/D8") (class "Default")
      (node (ref "J10") (pin "1") (pinfunction "1_1") (pintype "passive"))
      (node (ref "JP1") (pin "1") (pinfunction "1_1") (pintype "passive"))
      (node (ref "Q2") (pin "G") (pinfunction "G_G") (pintype "passive"))
      (node (ref "R2") (pin "P$2") (pinfunction "2_P$2") (pintype "passive"))
    )
    (net (code "30") (name "/D9") (class "Default")
      (node (ref "J10") (pin "2") (pinfunction "2_2") (pintype "passive"))
      (node (ref "J19") (pin "2") (pinfunction "2_2") (pintype "passive"))
      (node (ref "JP1") (pin "2") (pinfunction "2_2") (pintype "passive"))
      (node (ref "Q1") (pin "G") (pinfunction "G_G") (pintype "passive"))
      (node (ref "R1") (pin "P$2") (pinfunction "2_P$2") (pintype "passive"))
    )
    (net (code "31") (name "/D10") (class "Default")
      (node (ref "J10") (pin "3") (pinfunction "3_3") (pintype "passive"))
      (node (ref "J19") (pin "3") (pinfunction "3_3") (pintype "passive"))
      (node (ref "JP1") (pin "3") (pinfunction "3_3") (pintype "passive"))
    )
    (net (code "32") (name "/D11") (class "Default")
      (node (ref "J10") (pin "4") (pinfunction "4_4") (pintype "passive"))
      (node (ref "J19") (pin "4") (pinfunction "4_4") (pintype "passive"))
      (node (ref "JP1") (pin "4") (pinfunction "4_4") (pintype "passive"))
    )
    (net (code "33") (name "/D12") (class "Default")
      (node (ref "J10") (pin "5") (pinfunction "5_5") (pintype "passive"))
      (node (ref "J19") (pin "5") (pinfunction "5_5") (pintype "passive"))
      (node (ref "JP1") (pin "5") (pinfunction "5_5") (pintype "passive"))
    )
    (net (code "34") (name "/D13") (class "Default")
      (node (ref "J10") (pin "6") (pinfunction "6_6") (pintype "passive"))
      (node (ref "JP1") (pin "6") (pinfunction "6_6") (pintype "passive"))
      (node (ref "R14") (pin "P$2") (pinfunction "2_P$2") (pintype "passive"))
    )
    (net (code "35") (name "/D14") (class "Default")
      (node (ref "JP3") (pin "8") (pinfunction "8_8") (pintype "passive"))
    )
    (net (code "36") (name "/D15") (class "Default")
      (node (ref "JP3") (pin "7") (pinfunction "7_7") (pintype "passive"))
    )
    (net (code "37") (name "/D16") (class "Default")
      (node (ref "J12") (pin "6") (pinfunction "6_6") (pintype "passive"))
      (node (ref "JP3") (pin "6") (pinfunction "6_6") (pintype "passive"))
    )
    (net (code "38") (name "/D17") (class "Default")
      (node (ref "J12") (pin "5") (pinfunction "5_5") (pintype "passive"))
      (node (ref "JP3") (pin "5") (pinfunction "5_5") (pintype "passive"))
    )
    (net (code "39") (name "/D18") (class "Default")
      (node (ref "J12") (pin "4") (pinfunction "4_4") (pintype "passive"))
      (node (ref "JP3") (pin "4") (pinfunction "4_4") (pintype "passive"))
    )
    (net (code "40") (name "/D19") (class "Default")
      (node (ref "J12") (pin "3") (pinfunction "3_3") (pintype "passive"))
      (node (ref "JP3") (pin "3") (pinfunction "3_3") (pintype "passive"))
    )
    (net (code "41") (name "/D22") (class "Default")
      (node (ref "J13") (pin "3") (pinfunction "3_3") (pintype "passive"))
      (node (ref "JP5") (pin "1") (pinfunction "1_1") (pintype "passive"))
    )
    (net (code "42") (name "/D23") (class "Default")
      (node (ref "J14") (pin "3") (pinfunction "3_3") (pintype "passive"))
      (node (ref "JP6") (pin "16") (pinfunction "16_16") (pintype "passive"))
    )
    (net (code "43") (name "/D24") (class "Default")
      (node (ref "J15") (pin "3") (pinfunction "3_3") (pintype "passive"))
      (node (ref "JP5") (pin "2") (pinfunction "2_2") (pintype "passive"))
    )
    (net (code "44") (name "/D25") (class "Default")
      (node (ref "J16") (pin "3") (pinfunction "3_3") (pintype "passive"))
      (node (ref "JP6") (pin "15") (pinfunction "15_15") (pintype "passive"))
    )
    (net (code "45") (name "/D26") (class "Default")
      (node (ref "J17") (pin "3") (pinfunction "3_3") (pintype "passive"))
      (node (ref "JP5") (pin "3") (pinfunction "3_3") (pintype "passive"))
    )
    (net (code "46") (name "/D27") (class "Default")
      (node (ref "J18") (pin "3") (pinfunction "3_3") (pintype "passive"))
      (node (ref "JP6") (pin "14") (pinfunction "14_14") (pintype "passive"))
    )
    (net (code "47") (name "/D28") (class "Default")
      (node (ref "J20") (pin "3") (pinfunction "3_3") (pintype "passive"))
      (node (ref "JP5") (pin "4") (pinfunction "4_4") (pintype "passive"))
    )
    (net (code "48") (name "/D29") (class "Default")
      (node (ref "J21") (pin "3") (pinfunction "3_3") (pintype "passive"))
      (node (ref "JP6") (pin "13") (pinfunction "13_13") (pintype "passive"))
    )
    (net (code "49") (name "/D30") (class "Default")
      (node (ref "J23") (pin "3") (pinfunction "3_3") (pintype "passive"))
      (node (ref "JP5") (pin "5") (pinfunction "5_5") (pintype "passive"))
    )
    (net (code "50") (name "/D31") (class "Default")
      (node (ref "J24") (pin "3") (pinfunction "3_3") (pintype "passive"))
      (node (ref "JP6") (pin "12") (pinfunction "12_12") (pintype "passive"))
    )
    (net (code "51") (name "/D32") (class "Default")
      (node (ref "J25") (pin "3") (pinfunction "3_3") (pintype "passive"))
      (node (ref "JP5") (pin "6") (pinfunction "6_6") (pintype "passive"))
    )
    (net (code "52") (name "/D33") (class "Default")
      (node (ref "J26") (pin "3") (pinfunction "3_3") (pintype "passive"))
      (node (ref "JP6") (pin "11") (pinfunction "11_11") (pintype "passive"))
    )
    (net (code "53") (name "/D34") (class "Default")
      (node (ref "J27") (pin "3") (pinfunction "3_3") (pintype "passive"))
      (node (ref "JP5") (pin "7") (pinfunction "7_7") (pintype "passive"))
    )
    (net (code "54") (name "/D35") (class "Default")
      (node (ref "J28") (pin "3") (pinfunction "3_3") (pintype "passive"))
      (node (ref "JP6") (pin "10") (pinfunction "10_10") (pintype "passive"))
    )
    (net (code "55") (name "/D36") (class "Default")
      (node (ref "J29") (pin "3") (pinfunction "3_3") (pintype "passive"))
      (node (ref "JP5") (pin "8") (pinfunction "8_8") (pintype "passive"))
    )
    (net (code "56") (name "/D37") (class "Default")
      (node (ref "J30") (pin "3") (pinfunction "3_3") (pintype "passive"))
      (node (ref "JP6") (pin "9") (pinfunction "9_9") (pintype "passive"))
    )
    (net (code "57") (name "/D38") (class "Default")
      (node (ref "J31") (pin "3") (pinfunction "3_3") (pintype "passive"))
      (node (ref "JP5") (pin "9") (pinfunction "9_9") (pintype "passive"))
    )
    (net (code "58") (name "/D39") (class "Default")
      (node (ref "J32") (pin "3") (pinfunction "3_3") (pintype "passive"))
      (node (ref "JP6") (pin "8") (pinfunction "8_8") (pintype "passive"))
    )
    (net (code "59") (name "/D40") (class "Default")
      (node (ref "J33") (pin "3") (pinfunction "3_3") (pintype "passive"))
      (node (ref "JP5") (pin "10") (pinfunction "10_10") (pintype "passive"))
    )
    (net (code "60") (name "/D41") (class "Default")
      (node (ref "J34") (pin "3") (pinfunction "3_3") (pintype "passive"))
      (node (ref "JP6") (pin "7") (pinfunction "7_7") (pintype "passive"))
    )
    (net (code "61") (name "/D42") (class "Default")
      (node (ref "J35") (pin "3") (pinfunction "3_3") (pintype "passive"))
      (node (ref "JP5") (pin "11") (pinfunction "11_11") (pintype "passive"))
    )
    (net (code "62") (name "/D43") (class "Default")
      (node (ref "J36") (pin "3") (pinfunction "3_3") (pintype "passive"))
      (node (ref "JP6") (pin "6") (pinfunction "6_6") (pintype "passive"))
    )
    (net (code "63") (name "/D44") (class "Default")
      (node (ref "J37") (pin "3") (pinfunction "3_3") (pintype "passive"))
      (node (ref "JP5") (pin "12") (pinfunction "12_12") (pintype "passive"))
    )
    (net (code "64") (name "/D45") (class "Default")
      (node (ref "J38") (pin "3") (pinfunction "3_3") (pintype "passive"))
      (node (ref "JP6") (pin "5") (pinfunction "5_5") (pintype "passive"))
    )
    (net (code "65") (name "/D46") (class "Default")
      (node (ref "J39") (pin "3") (pinfunction "3_3") (pintype "passive"))
      (node (ref "JP5") (pin "13") (pinfunction "13_13") (pintype "passive"))
    )
    (net (code "66") (name "/D47") (class "Default")
      (node (ref "J40") (pin "3") (pinfunction "3_3") (pintype "passive"))
      (node (ref "JP6") (pin "4") (pinfunction "4_4") (pintype "passive"))
    )
    (net (code "67") (name "/D48") (class "Default")
      (node (ref "J41") (pin "3") (pinfunction "3_3") (pintype "passive"))
      (node (ref "JP5") (pin "14") (pinfunction "14_14") (pintype "passive"))
    )
    (net (code "68") (name "/D49") (class "Default")
      (node (ref "J42") (pin "3") (pinfunction "3_3") (pintype "passive"))
      (node (ref "JP6") (pin "3") (pinfunction "3_3") (pintype "passive"))
    )
    (net (code "69") (name "/D50") (class "Default")
      (node (ref "J48") (pin "3") (pinfunction "3_3") (pintype "passive"))
      (node (ref "JP5") (pin "15") (pinfunction "15_15") (pintype "passive"))
    )
    (net (code "70") (name "/D51") (class "Default")
      (node (ref "J49") (pin "3") (pinfunction "3_3") (pintype "passive"))
      (node (ref "JP6") (pin "2") (pinfunction "2_2") (pintype "passive"))
    )
    (net (code "71") (name "/D52") (class "Default")
      (node (ref "J50") (pin "3") (pinfunction "3_3") (pintype "passive"))
      (node (ref "JP5") (pin "16") (pinfunction "16_16") (pintype "passive"))
    )
    (net (code "72") (name "/D53") (class "Default")
      (node (ref "J51") (pin "3") (pinfunction "3_3") (pintype "passive"))
      (node (ref "JP6") (pin "1") (pinfunction "1_1") (pintype "passive"))
    )
    (net (code "73") (name "/RES") (class "Default")
      (node (ref "J52") (pin "1") (pinfunction "1_1") (pintype "passive"))
      (node (ref "JP8") (pin "1") (pinfunction "1_1") (pintype "passive"))
      (node (ref "R15") (pin "P$1") (pinfunction "1_P$1") (pintype "passive"))
      (node (ref "S1") (pin "3") (pinfunction "3_3") (pintype "passive"))
      (node (ref "S1") (pin "4") (pinfunction "4_4") (pintype "passive"))
    )
    (net (code "74") (name "/RX0") (class "Default")
      (node (ref "J11") (pin "1") (pinfunction "1_1") (pintype "passive"))
      (node (ref "JP2") (pin "1") (pinfunction "1_1") (pintype "passive"))
    )
    (net (code "75") (name "/SCL") (class "Default")
      (node (ref "J12") (pin "1") (pinfunction "1_1") (pintype "passive"))
      (node (ref "JP3") (pin "1") (pinfunction "1_1") (pintype "passive"))
    )
    (net (code "76") (name "/SDA") (class "Default")
      (node (ref "J12") (pin "2") (pinfunction "2_2") (pintype "passive"))
      (node (ref "JP3") (pin "2") (pinfunction "2_2") (pintype "passive"))
    )
    (net (code "77") (name "/TX1") (class "Default")
      (node (ref "J11") (pin "2") (pinfunction "2_2") (pintype "passive"))
      (node (ref "JP2") (pin "2") (pinfunction "2_2") (pintype "passive"))
    )
    (net (code "78") (name "GND") (class "Default")
      (node (ref "IC1") (pin "2") (pinfunction "GND_2") (pintype "passive"))
      (node (ref "J10") (pin "7") (pinfunction "7_7") (pintype "passive"))
      (node (ref "J13") (pin "2") (pinfunction "2_2") (pintype "passive"))
      (node (ref "J14") (pin "2") (pinfunction "2_2") (pintype "passive"))
      (node (ref "J15") (pin "2") (pinfunction "2_2") (pintype "passive"))
      (node (ref "J16") (pin "2") (pinfunction "2_2") (pintype "passive"))
      (node (ref "J17") (pin "2") (pinfunction "2_2") (pintype "passive"))
      (node (ref "J18") (pin "2") (pinfunction "2_2") (pintype "passive"))
      (node (ref "J19") (pin "6") (pinfunction "6_6") (pintype "passive"))
      (node (ref "J20") (pin "2") (pinfunction "2_2") (pintype "passive"))
      (node (ref "J21") (pin "2") (pinfunction "2_2") (pintype "passive"))
      (node (ref "J22") (pin "2") (pinfunction "2_2") (pintype "passive"))
      (node (ref "J22") (pin "3") (pinfunction "3_3") (pintype "passive"))
      (node (ref "J23") (pin "2") (pinfunction "2_2") (pintype "passive"))
      (node (ref "J24") (pin "2") (pinfunction "2_2") (pintype "passive"))
      (node (ref "J25") (pin "2") (pinfunction "2_2") (pintype "passive"))
      (node (ref "J26") (pin "2") (pinfunction "2_2") (pintype "passive"))
      (node (ref "J27") (pin "2") (pinfunction "2_2") (pintype "passive"))
      (node (ref "J28") (pin "2") (pinfunction "2_2") (pintype "passive"))
      (node (ref "J29") (pin "2") (pinfunction "2_2") (pintype "passive"))
      (node (ref "J30") (pin "2") (pinfunction "2_2") (pintype "passive"))
      (node (ref "J31") (pin "2") (pinfunction "2_2") (pintype "passive"))
      (node (ref "J32") (pin "2") (pinfunction "2_2") (pintype "passive"))
      (node (ref "J33") (pin "2") (pinfunction "2_2") (pintype "passive"))
      (node (ref "J34") (pin "2") (pinfunction "2_2") (pintype "passive"))
      (node (ref "J35") (pin "2") (pinfunction "2_2") (pintype "passive"))
      (node (ref "J36") (pin "2") (pinfunction "2_2") (pintype "passive"))
      (node (ref "J37") (pin "2") (pinfunction "2_2") (pintype "passive"))
      (node (ref "J38") (pin "2") (pinfunction "2_2") (pintype "passive"))
      (node (ref "J39") (pin "2") (pinfunction "2_2") (pintype "passive"))
      (node (ref "J40") (pin "2") (pinfunction "2_2") (pintype "passive"))
      (node (ref "J41") (pin "2") (pinfunction "2_2") (pintype "passive"))
      (node (ref "J42") (pin "2") (pinfunction "2_2") (pintype "passive"))
      (node (ref "J43") (pin "1") (pinfunction "1_1") (pintype "passive"))
      (node (ref "J44") (pin "1") (pinfunction "1_1") (pintype "passive"))
      (node (ref "J45") (pin "1") (pinfunction "1_1") (pintype "passive"))
      (node (ref "J46") (pin "1") (pinfunction "1_1") (pintype "passive"))
      (node (ref "J47") (pin "2") (pinfunction "2_2") (pintype "passive"))
      (node (ref "J48") (pin "2") (pinfunction "2_2") (pintype "passive"))
      (node (ref "J49") (pin "2") (pinfunction "2_2") (pintype "passive"))
      (node (ref "J50") (pin "2") (pinfunction "2_2") (pintype "passive"))
      (node (ref "J51") (pin "2") (pinfunction "2_2") (pintype "passive"))
      (node (ref "J52") (pin "4") (pinfunction "4_4") (pintype "passive"))
      (node (ref "J52") (pin "5") (pinfunction "5_5") (pintype "passive"))
      (node (ref "J9") (pin "1") (pinfunction "1_1") (pintype "bidirectional"))
      (node (ref "JP1") (pin "7") (pinfunction "7_7") (pintype "passive"))
      (node (ref "JP7") (pin "1") (pinfunction "1_1") (pintype "passive"))
      (node (ref "JP7") (pin "2") (pinfunction "2_2") (pintype "passive"))
      (node (ref "JP8") (pin "4") (pinfunction "4_4") (pintype "passive"))
      (node (ref "JP8") (pin "5") (pinfunction "5_5") (pintype "passive"))
      (node (ref "LED1") (pin "K") (pinfunction "C_K") (pintype "passive"))
      (node (ref "LED2") (pin "K") (pinfunction "C_K") (pintype "passive"))
      (node (ref "Q1") (pin "S") (pinfunction "S_S") (pintype "passive"))
      (node (ref "Q2") (pin "S") (pinfunction "S_S") (pintype "passive"))
      (node (ref "Q3") (pin "S") (pinfunction "S_S") (pintype "passive"))
      (node (ref "Q4") (pin "S") (pinfunction "S_S") (pintype "passive"))
      (node (ref "Q5") (pin "S") (pinfunction "S_S") (pintype "passive"))
      (node (ref "Q6") (pin "S") (pinfunction "S_S") (pintype "passive"))
      (node (ref "Q7") (pin "S") (pinfunction "S_S") (pintype "passive"))
      (node (ref "Q8") (pin "S") (pinfunction "S_S") (pintype "passive"))
      (node (ref "R1") (pin "P$1") (pinfunction "1_P$1") (pintype "passive"))
      (node (ref "R16") (pin "P$1") (pinfunction "1_P$1") (pintype "passive"))
      (node (ref "R18") (pin "P$1") (pinfunction "1_P$1") (pintype "passive"))
      (node (ref "R2") (pin "P$1") (pinfunction "1_P$1") (pintype "passive"))
      (node (ref "R3") (pin "P$1") (pinfunction "1_P$1") (pintype "passive"))
      (node (ref "R4") (pin "P$1") (pinfunction "1_P$1") (pintype "passive"))
      (node (ref "R5") (pin "P$1") (pinfunction "1_P$1") (pintype "passive"))
      (node (ref "R6") (pin "P$1") (pinfunction "1_P$1") (pintype "passive"))
      (node (ref "R7") (pin "P$1") (pinfunction "1_P$1") (pintype "passive"))
      (node (ref "R8") (pin "P$1") (pinfunction "1_P$1") (pintype "passive"))
      (node (ref "S1") (pin "1") (pinfunction "1_1") (pintype "passive"))
      (node (ref "S1") (pin "2") (pinfunction "2_2") (pintype "passive"))
    )
    (net (code "79") (name "Net-(D1-PadA)") (class "Default")
      (node (ref "D1") (pin "A") (pinfunction "A_A") (pintype "passive"))
      (node (ref "D9") (pin "A") (pinfunction "A_A") (pintype "passive"))
      (node (ref "J1") (pin "1") (pinfunction "1_1") (pintype "bidirectional"))
    )
    (net (code "80") (name "Net-(D9-PadC)") (class "Default")
      (node (ref "D9") (pin "C") (pinfunction "C_C") (pintype "passive"))
      (node (ref "Q1") (pin "D") (pinfunction "D_D") (pintype "passive"))
    )
    (net (code "81") (name "Net-(D10-PadA)") (class "Default")
      (node (ref "D10") (pin "A") (pinfunction "A_A") (pintype "passive"))
      (node (ref "D2") (pin "A") (pinfunction "A_A") (pintype "passive"))
      (node (ref "J2") (pin "1") (pinfunction "1_1") (pintype "bidirectional"))
    )
    (net (code "82") (name "Net-(D10-PadC)") (class "Default")
      (node (ref "D10") (pin "C") (pinfunction "C_C") (pintype "passive"))
      (node (ref "Q2") (pin "D") (pinfunction "D_D") (pintype "passive"))
    )
    (net (code "83") (name "Net-(D11-PadA)") (class "Default")
      (node (ref "D11") (pin "A") (pinfunction "A_A") (pintype "passive"))
      (node (ref "D3") (pin "A") (pinfunction "A_A") (pintype "passive"))
      (node (ref "J3") (pin "1") (pinfunction "1_1") (pintype "bidirectional"))
    )
    (net (code "84") (name "Net-(D11-PadC)") (class "Default")
      (node (ref "D11") (pin "C") (pinfunction "C_C") (pintype "passive"))
      (node (ref "Q3") (pin "D") (pinfunction "D_D") (pintype "passive"))
    )
    (net (code "85") (name "Net-(D12-PadA)") (class "Default")
      (node (ref "D12") (pin "A") (pinfunction "A_A") (pintype "passive"))
      (node (ref "D4") (pin "A") (pinfunction "A_A") (pintype "passive"))
      (node (ref "J4") (pin "1") (pinfunction "1_1") (pintype "bidirectional"))
    )
    (net (code "86") (name "Net-(D12-PadC)") (class "Default")
      (node (ref "D12") (pin "C") (pinfunction "C_C") (pintype "passive"))
      (node (ref "Q4") (pin "D") (pinfunction "D_D") (pintype "passive"))
    )
    (net (code "87") (name "Net-(D13-PadA)") (class "Default")
      (node (ref "D13") (pin "A") (pinfunction "A_A") (pintype "passive"))
      (node (ref "D5") (pin "A") (pinfunction "A_A") (pintype "passive"))
      (node (ref "J5") (pin "1") (pinfunction "1_1") (pintype "bidirectional"))
    )
    (net (code "88") (name "Net-(D13-PadC)") (class "Default")
      (node (ref "D13") (pin "C") (pinfunction "C_C") (pintype "passive"))
      (node (ref "Q5") (pin "D") (pinfunction "D_D") (pintype "passive"))
    )
    (net (code "89") (name "Net-(D14-PadA)") (class "Default")
      (node (ref "D14") (pin "A") (pinfunction "A_A") (pintype "passive"))
      (node (ref "D6") (pin "A") (pinfunction "A_A") (pintype "passive"))
      (node (ref "J6") (pin "1") (pinfunction "1_1") (pintype "bidirectional"))
    )
    (net (code "90") (name "Net-(D14-PadC)") (class "Default")
      (node (ref "D14") (pin "C") (pinfunction "C_C") (pintype "passive"))
      (node (ref "Q6") (pin "D") (pinfunction "D_D") (pintype "passive"))
    )
    (net (code "91") (name "Net-(D15-PadA)") (class "Default")
      (node (ref "D15") (pin "A") (pinfunction "A_A") (pintype "passive"))
      (node (ref "D7") (pin "A") (pinfunction "A_A") (pintype "passive"))
      (node (ref "J7") (pin "1") (pinfunction "1_1") (pintype "bidirectional"))
    )
    (net (code "92") (name "Net-(D15-PadC)") (class "Default")
      (node (ref "D15") (pin "C") (pinfunction "C_C") (pintype "passive"))
      (node (ref "Q7") (pin "D") (pinfunction "D_D") (pintype "passive"))
    )
    (net (code "93") (name "Net-(D16-PadA)") (class "Default")
      (node (ref "D16") (pin "A") (pinfunction "A_A") (pintype "passive"))
      (node (ref "D8") (pin "A") (pinfunction "A_A") (pintype "passive"))
      (node (ref "J8") (pin "1") (pinfunction "1_1") (pintype "bidirectional"))
    )
    (net (code "94") (name "Net-(D16-PadC)") (class "Default")
      (node (ref "D16") (pin "C") (pinfunction "C_C") (pintype "passive"))
      (node (ref "Q8") (pin "D") (pinfunction "D_D") (pintype "passive"))
    )
    (net (code "95") (name "Net-(IC1-VO)") (class "Default")
      (node (ref "IC1") (pin "3") (pinfunction "VO_3") (pintype "passive"))
      (node (ref "J22") (pin "1") (pinfunction "1_1") (pintype "passive"))
    )
    (net (code "96") (name "Net-(IC2-ADJ)") (class "Default")
      (node (ref "IC2") (pin "1") (pinfunction "ADJ_1") (pintype "input"))
      (node (ref "R18") (pin "P$2") (pinfunction "2_P$2") (pintype "passive"))
      (node (ref "R19") (pin "P$2") (pinfunction "2_P$2") (pintype "passive"))
    )
    (net (code "97") (name "Net-(IC4-ADJ)") (class "Default")
      (node (ref "IC4") (pin "1") (pinfunction "ADJ_1") (pintype "input"))
      (node (ref "R16") (pin "P$2") (pinfunction "2_P$2") (pintype "passive"))
      (node (ref "R17") (pin "P$2") (pinfunction "2_P$2") (pintype "passive"))
    )
    (net (code "98") (name "Net-(R13-1)") (class "Default")
      (node (ref "LED2") (pin "A") (pinfunction "A_A") (pintype "passive"))
      (node (ref "R13") (pin "P$1") (pinfunction "1_P$1") (pintype "passive"))
    )
    (net (code "99") (name "Net-(R14-1)") (class "Default")
      (node (ref "LED1") (pin "A") (pinfunction "A_A") (pintype "passive"))
      (node (ref "R14") (pin "P$1") (pinfunction "1_P$1") (pintype "passive"))
    )
    (net (code "100") (name "unconnected-(J47-Pad8)") (class "Default")
      (node (ref "J47") (pin "8") (pinfunction "8_8") (pintype "passive"))
    )
  )
)
